# PSU2.net
KiCad netlist of a schematic drawn in Altium Designer
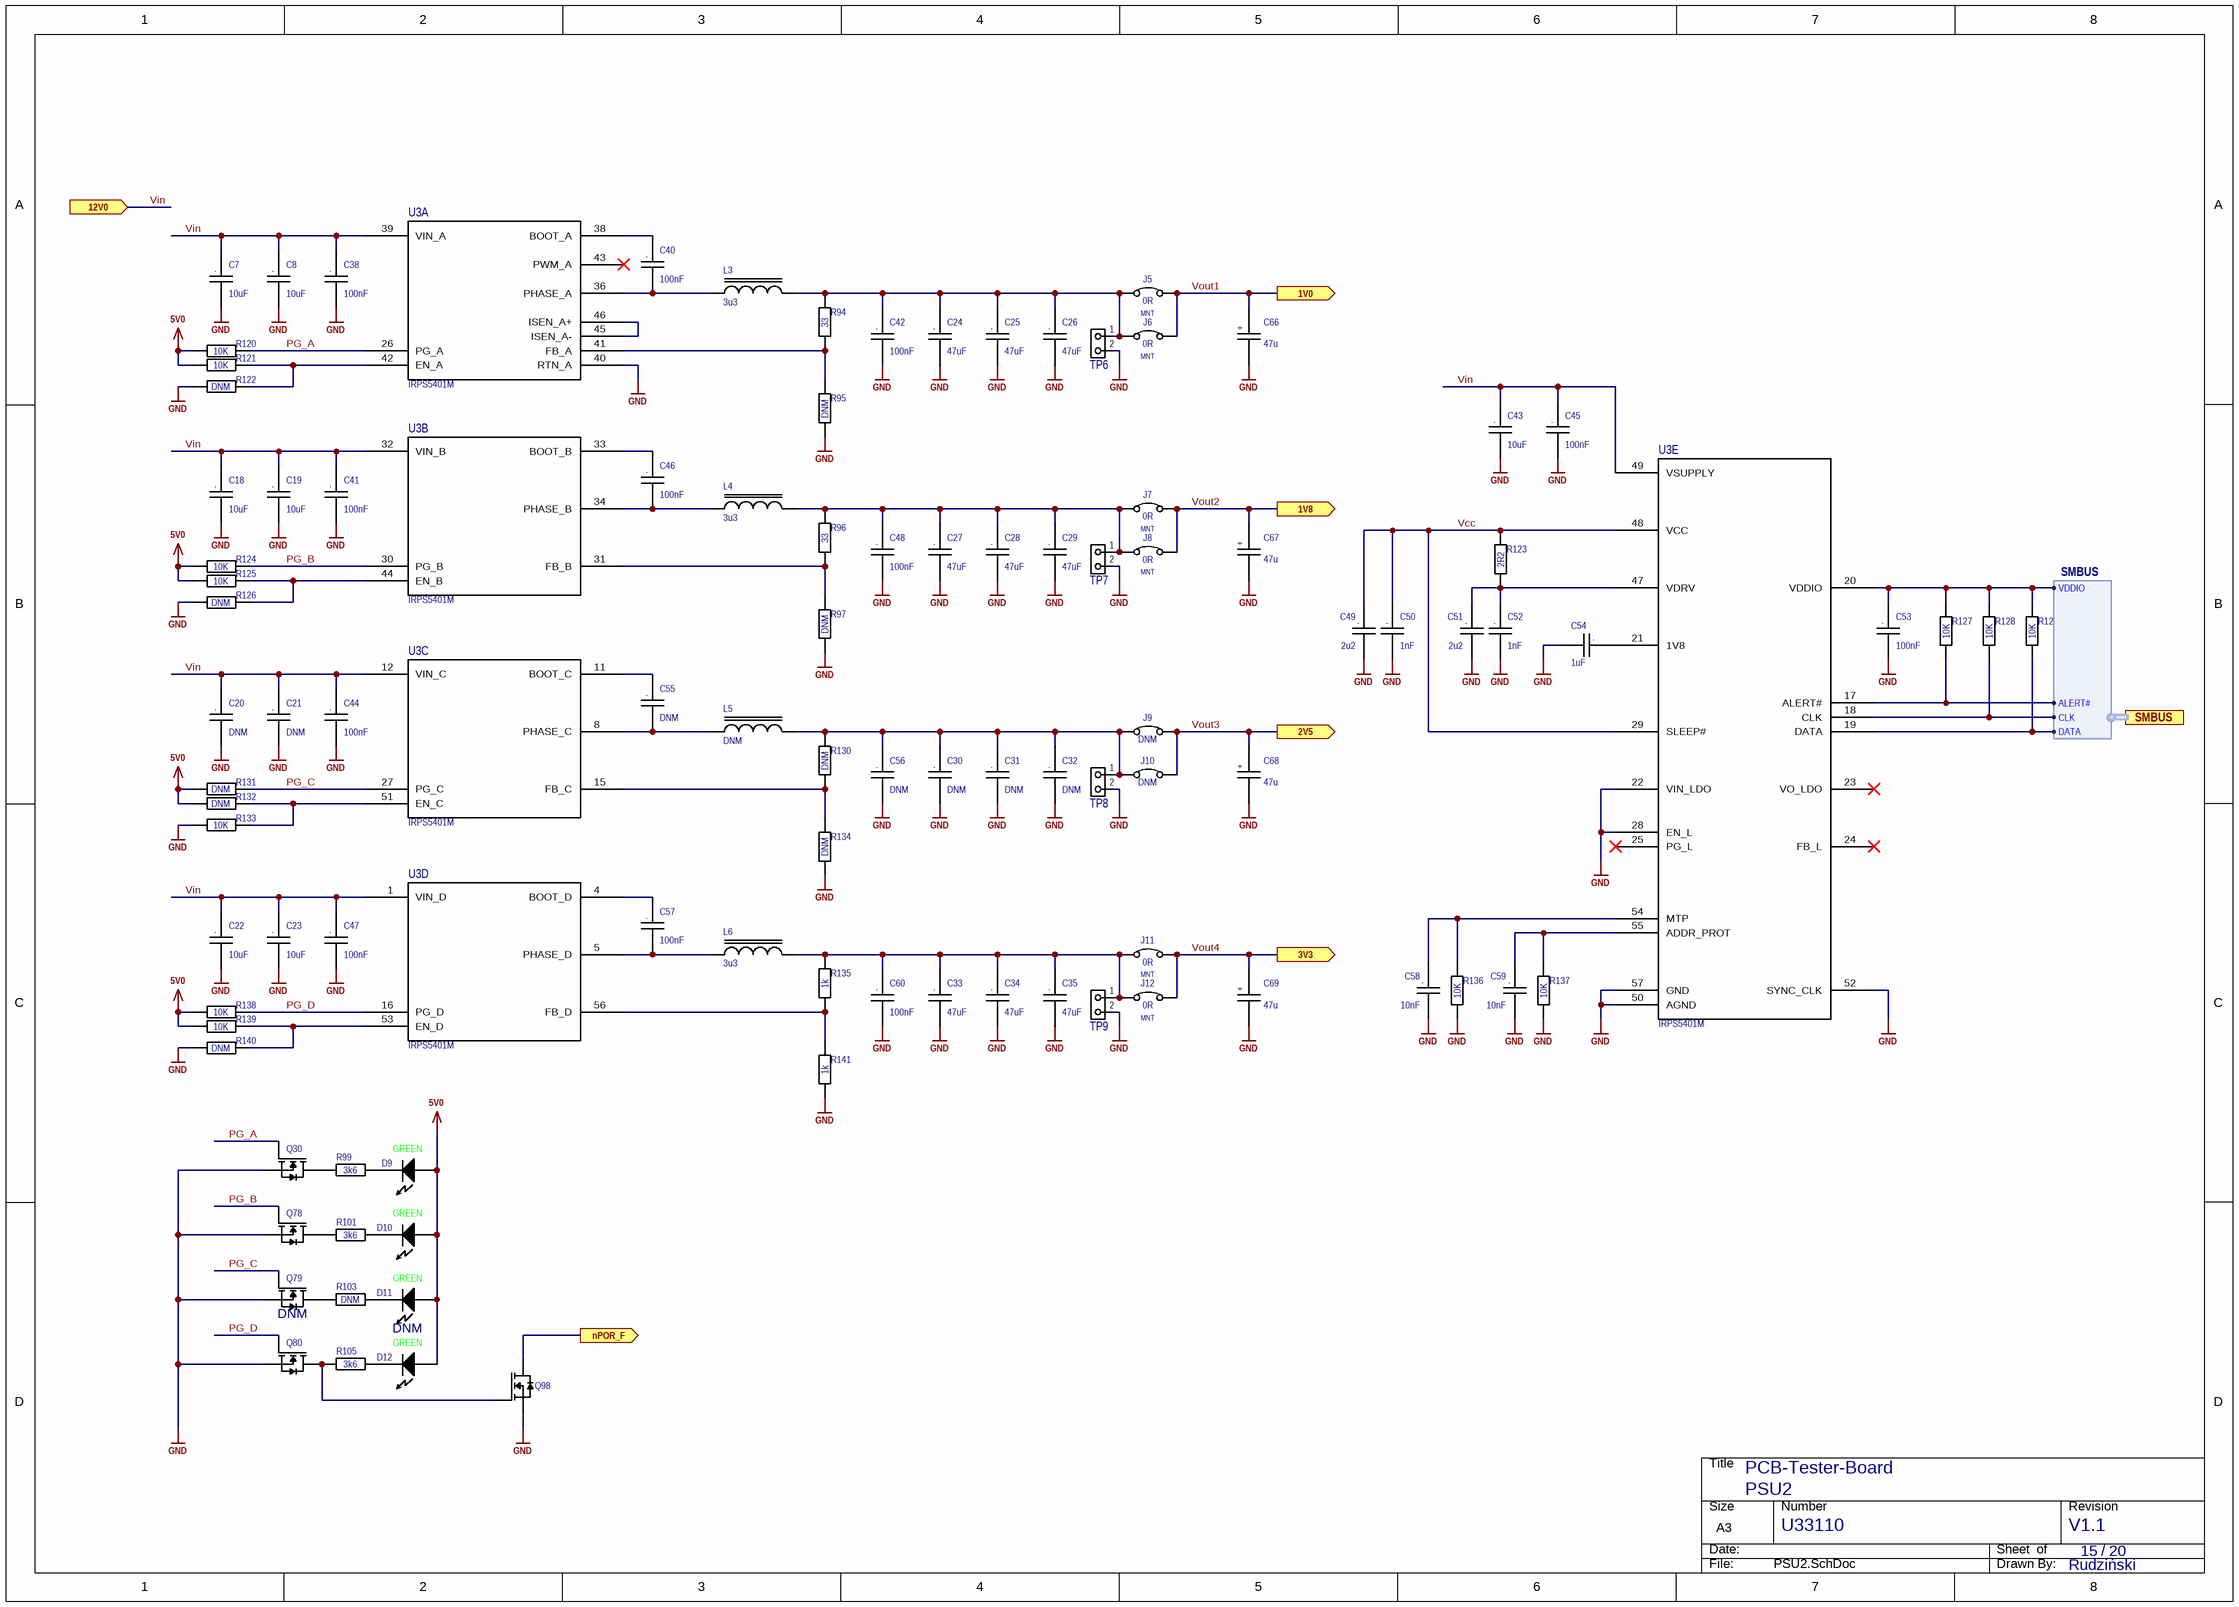
[diagram p0: PSU2.SchDoc]

(export (version "E")
  (design (tool "Eeschema 10.0.6"))
  (components
    (comp (ref "C7")
      (value "10uF")
      (footprint "C1206 Reflow")
      (description "CAP CER 10UF 25V X7R 1206")
      (fields
        (field (name "TOLERANCE") "±10%")
        (field (name "02. DISTRIBUTOR PART NUMBER") "445-7705-6-ND")
        (field (name "13. CREATED DATE/NAME") "AUG2018/Hören")
      )
      (libsource (lib "chickenfood") (part "C"))
    )
    (comp (ref "C8")
      (value "10uF")
      (footprint "C1206 Reflow")
      (description "CAP CER 10UF 25V X7R 1206")
      (fields
        (field (name "TOLERANCE") "±10%")
        (field (name "02. DISTRIBUTOR PART NUMBER") "445-7705-6-ND")
        (field (name "13. CREATED DATE/NAME") "AUG2018/Hören")
      )
      (libsource (lib "chickenfood") (part "C"))
    )
    (comp (ref "C18")
      (value "10uF")
      (footprint "C1206 Reflow")
      (description "CAP CER 10UF 25V X7R 1206")
      (fields
        (field (name "TOLERANCE") "±10%")
        (field (name "02. DISTRIBUTOR PART NUMBER") "445-7705-6-ND")
        (field (name "13. CREATED DATE/NAME") "AUG2018/Hören")
      )
      (libsource (lib "chickenfood") (part "C"))
    )
    (comp (ref "C19")
      (value "10uF")
      (footprint "C1206 Reflow")
      (description "CAP CER 10UF 25V X7R 1206")
      (fields
        (field (name "TOLERANCE") "±10%")
        (field (name "02. DISTRIBUTOR PART NUMBER") "445-7705-6-ND")
        (field (name "13. CREATED DATE/NAME") "AUG2018/Hören")
      )
      (libsource (lib "chickenfood") (part "C"))
    )
    (comp (ref "C20")
      (value "DNM")
      (footprint "C1206 Reflow")
      (description "CAP CER 10UF 25V X7R 1206")
      (fields
        (field (name "TOLERANCE") "±10%")
        (field (name "02. DISTRIBUTOR PART NUMBER") "445-7705-6-ND")
        (field (name "13. CREATED DATE/NAME") "AUG2018/Hören")
      )
      (libsource (lib "chickenfood") (part "C"))
    )
    (comp (ref "C21")
      (value "DNM")
      (footprint "C1206 Reflow")
      (description "CAP CER 10UF 25V X7R 1206")
      (fields
        (field (name "TOLERANCE") "±10%")
        (field (name "02. DISTRIBUTOR PART NUMBER") "445-7705-6-ND")
        (field (name "13. CREATED DATE/NAME") "AUG2018/Hören")
      )
      (libsource (lib "chickenfood") (part "C"))
    )
    (comp (ref "C22")
      (value "10uF")
      (footprint "C1206 Reflow")
      (description "CAP CER 10UF 25V X7R 1206")
      (fields
        (field (name "TOLERANCE") "±10%")
        (field (name "02. DISTRIBUTOR PART NUMBER") "445-7705-6-ND")
        (field (name "13. CREATED DATE/NAME") "AUG2018/Hören")
      )
      (libsource (lib "chickenfood") (part "C"))
    )
    (comp (ref "C23")
      (value "10uF")
      (footprint "C1206 Reflow")
      (description "CAP CER 10UF 25V X7R 1206")
      (fields
        (field (name "TOLERANCE") "±10%")
        (field (name "02. DISTRIBUTOR PART NUMBER") "445-7705-6-ND")
        (field (name "13. CREATED DATE/NAME") "AUG2018/Hören")
      )
      (libsource (lib "chickenfood") (part "C"))
    )
    (comp (ref "C24")
      (value "47uF")
      (footprint "C1210 Reflow")
      (description "CAP CER 47UF 10V X5R 1210")
      (fields
        (field (name "TOLERANCE") "±20%")
        (field (name "02. DISTRIBUTOR PART NUMBER") "1276-3380-6-ND")
        (field (name "13. CREATED DATE/NAME") "AUG2018/Hören")
      )
      (libsource (lib "chickenfood") (part "C"))
    )
    (comp (ref "C25")
      (value "47uF")
      (footprint "C1210 Reflow")
      (description "CAP CER 47UF 10V X5R 1210")
      (fields
        (field (name "TOLERANCE") "±20%")
        (field (name "02. DISTRIBUTOR PART NUMBER") "1276-3380-6-ND")
        (field (name "13. CREATED DATE/NAME") "AUG2018/Hören")
      )
      (libsource (lib "chickenfood") (part "C"))
    )
    (comp (ref "C26")
      (value "47uF")
      (footprint "C1210 Reflow")
      (description "CAP CER 47UF 10V X5R 1210")
      (fields
        (field (name "TOLERANCE") "±20%")
        (field (name "02. DISTRIBUTOR PART NUMBER") "1276-3380-6-ND")
        (field (name "13. CREATED DATE/NAME") "AUG2018/Hören")
      )
      (libsource (lib "chickenfood") (part "C"))
    )
    (comp (ref "C27")
      (value "47uF")
      (footprint "C1210 Reflow")
      (description "CAP CER 47UF 10V X5R 1210")
      (fields
        (field (name "TOLERANCE") "±20%")
        (field (name "02. DISTRIBUTOR PART NUMBER") "1276-3380-6-ND")
        (field (name "13. CREATED DATE/NAME") "AUG2018/Hören")
      )
      (libsource (lib "chickenfood") (part "C"))
    )
    (comp (ref "C28")
      (value "47uF")
      (footprint "C1210 Reflow")
      (description "CAP CER 47UF 10V X5R 1210")
      (fields
        (field (name "TOLERANCE") "±20%")
        (field (name "02. DISTRIBUTOR PART NUMBER") "1276-3380-6-ND")
        (field (name "13. CREATED DATE/NAME") "AUG2018/Hören")
      )
      (libsource (lib "chickenfood") (part "C"))
    )
    (comp (ref "C29")
      (value "47uF")
      (footprint "C1210 Reflow")
      (description "CAP CER 47UF 10V X5R 1210")
      (fields
        (field (name "TOLERANCE") "±20%")
        (field (name "02. DISTRIBUTOR PART NUMBER") "1276-3380-6-ND")
        (field (name "13. CREATED DATE/NAME") "AUG2018/Hören")
      )
      (libsource (lib "chickenfood") (part "C"))
    )
    (comp (ref "C30")
      (value "DNM")
      (footprint "C1210 Reflow")
      (description "CAP CER 47UF 10V X5R 1210")
      (fields
        (field (name "TOLERANCE") "±20%")
        (field (name "02. DISTRIBUTOR PART NUMBER") "1276-3380-6-ND")
        (field (name "13. CREATED DATE/NAME") "AUG2018/Hören")
      )
      (libsource (lib "chickenfood") (part "C"))
    )
    (comp (ref "C31")
      (value "DNM")
      (footprint "C1210 Reflow")
      (description "CAP CER 47UF 10V X5R 1210")
      (fields
        (field (name "TOLERANCE") "±20%")
        (field (name "02. DISTRIBUTOR PART NUMBER") "1276-3380-6-ND")
        (field (name "13. CREATED DATE/NAME") "AUG2018/Hören")
      )
      (libsource (lib "chickenfood") (part "C"))
    )
    (comp (ref "C32")
      (value "DNM")
      (footprint "C1210 Reflow")
      (description "CAP CER 47UF 10V X5R 1210")
      (fields
        (field (name "TOLERANCE") "±20%")
        (field (name "02. DISTRIBUTOR PART NUMBER") "1276-3380-6-ND")
        (field (name "13. CREATED DATE/NAME") "AUG2018/Hören")
      )
      (libsource (lib "chickenfood") (part "C"))
    )
    (comp (ref "C33")
      (value "47uF")
      (footprint "C1210 Reflow")
      (description "CAP CER 47UF 10V X5R 1210")
      (fields
        (field (name "TOLERANCE") "±20%")
        (field (name "02. DISTRIBUTOR PART NUMBER") "1276-3380-6-ND")
        (field (name "13. CREATED DATE/NAME") "AUG2018/Hören")
      )
      (libsource (lib "chickenfood") (part "C"))
    )
    (comp (ref "C34")
      (value "47uF")
      (footprint "C1210 Reflow")
      (description "CAP CER 47UF 10V X5R 1210")
      (fields
        (field (name "TOLERANCE") "±20%")
        (field (name "02. DISTRIBUTOR PART NUMBER") "1276-3380-6-ND")
        (field (name "13. CREATED DATE/NAME") "AUG2018/Hören")
      )
      (libsource (lib "chickenfood") (part "C"))
    )
    (comp (ref "C35")
      (value "47uF")
      (footprint "C1210 Reflow")
      (description "CAP CER 47UF 10V X5R 1210")
      (fields
        (field (name "TOLERANCE") "±20%")
        (field (name "02. DISTRIBUTOR PART NUMBER") "1276-3380-6-ND")
        (field (name "13. CREATED DATE/NAME") "AUG2018/Hören")
      )
      (libsource (lib "chickenfood") (part "C"))
    )
    (comp (ref "C38")
      (value "100nF")
      (footprint "C0402 Reflow")
      (description "CAP CER 0.1UF 25V X7R 0402")
      (fields
        (field (name "TOLERANCE") "±10%")
        (field (name "02. DISTRIBUTOR PART NUMBER") "311-2077-6-ND")
        (field (name "13. CREATED DATE/NAME") "AUG2018/Hören")
      )
      (libsource (lib "chickenfood") (part "C"))
    )
    (comp (ref "C40")
      (value "100nF")
      (footprint "C0402 Reflow")
      (description "CAP CER 0.1UF 25V X7R 0402")
      (fields
        (field (name "TOLERANCE") "±10%")
        (field (name "02. DISTRIBUTOR PART NUMBER") "311-2077-6-ND")
        (field (name "13. CREATED DATE/NAME") "AUG2018/Hören")
      )
      (libsource (lib "chickenfood") (part "C"))
    )
    (comp (ref "C41")
      (value "100nF")
      (footprint "C0402 Reflow")
      (description "CAP CER 0.1UF 25V X7R 0402")
      (fields
        (field (name "TOLERANCE") "±10%")
        (field (name "02. DISTRIBUTOR PART NUMBER") "311-2077-6-ND")
        (field (name "13. CREATED DATE/NAME") "AUG2018/Hören")
      )
      (libsource (lib "chickenfood") (part "C"))
    )
    (comp (ref "C42")
      (value "100nF")
      (footprint "C0402 Reflow")
      (description "CAP CER 0.1UF 25V X7R 0402")
      (fields
        (field (name "TOLERANCE") "±10%")
        (field (name "02. DISTRIBUTOR PART NUMBER") "311-2077-6-ND")
        (field (name "13. CREATED DATE/NAME") "AUG2018/Hören")
      )
      (libsource (lib "chickenfood") (part "C"))
    )
    (comp (ref "C43")
      (value "10uF")
      (footprint "C1206 Reflow")
      (description "CAP CER 10UF 25V X7R 1206")
      (fields
        (field (name "TOLERANCE") "±10%")
        (field (name "02. DISTRIBUTOR PART NUMBER") "445-7705-6-ND")
        (field (name "13. CREATED DATE/NAME") "AUG2018/Hören")
      )
      (libsource (lib "chickenfood") (part "C"))
    )
    (comp (ref "C44")
      (value "100nF")
      (footprint "C0402 Reflow")
      (description "CAP CER 0.1UF 25V X7R 0402")
      (fields
        (field (name "TOLERANCE") "±10%")
        (field (name "02. DISTRIBUTOR PART NUMBER") "311-2077-6-ND")
        (field (name "13. CREATED DATE/NAME") "AUG2018/Hören")
      )
      (libsource (lib "chickenfood") (part "C"))
    )
    (comp (ref "C45")
      (value "100nF")
      (footprint "C0402 Reflow")
      (description "CAP CER 0.1UF 25V X7R 0402")
      (fields
        (field (name "TOLERANCE") "±10%")
        (field (name "02. DISTRIBUTOR PART NUMBER") "311-2077-6-ND")
        (field (name "13. CREATED DATE/NAME") "AUG2018/Hören")
      )
      (libsource (lib "chickenfood") (part "C"))
    )
    (comp (ref "C46")
      (value "100nF")
      (footprint "C0402 Reflow")
      (description "CAP CER 0.1UF 25V X7R 0402")
      (fields
        (field (name "TOLERANCE") "±10%")
        (field (name "02. DISTRIBUTOR PART NUMBER") "311-2077-6-ND")
        (field (name "13. CREATED DATE/NAME") "AUG2018/Hören")
      )
      (libsource (lib "chickenfood") (part "C"))
    )
    (comp (ref "C47")
      (value "100nF")
      (footprint "C0402 Reflow")
      (description "CAP CER 0.1UF 25V X7R 0402")
      (fields
        (field (name "TOLERANCE") "±10%")
        (field (name "02. DISTRIBUTOR PART NUMBER") "311-2077-6-ND")
        (field (name "13. CREATED DATE/NAME") "AUG2018/Hören")
      )
      (libsource (lib "chickenfood") (part "C"))
    )
    (comp (ref "C48")
      (value "100nF")
      (footprint "C0402 Reflow")
      (description "CAP CER 0.1UF 25V X7R 0402")
      (fields
        (field (name "TOLERANCE") "±10%")
        (field (name "02. DISTRIBUTOR PART NUMBER") "311-2077-6-ND")
        (field (name "13. CREATED DATE/NAME") "AUG2018/Hören")
      )
      (libsource (lib "chickenfood") (part "C"))
    )
    (comp (ref "C49")
      (value "2u2")
      (footprint "C0805 Reflow")
      (description "CAP CER 2.2UF 10V X7R 0805")
      (fields
        (field (name "02. DISTRIBUTOR PART NUMBER") "1276-1188-1-ND")
        (field (name "07. MANUFACTURER  PART NUMBER") "CL21B225KPFNNNE")
      )
      (libsource (lib "PCB-Tester-Board-V1") (part "C_11"))
    )
    (comp (ref "C50")
      (value "1nF")
      (footprint "C0402 Reflow")
      (description "CAP CER 1000PF 25V X7R 0402")
      (fields
        (field (name "TOLERANCE") "±10%")
        (field (name "02. DISTRIBUTOR PART NUMBER") "399-1031-6-ND")
        (field (name "13. CREATED DATE/NAME") "AUG2018/Hören")
      )
      (libsource (lib "PCB-Tester-Board-V1") (part "C_7"))
    )
    (comp (ref "C51")
      (value "2u2")
      (footprint "C0805 Reflow")
      (description "CAP CER 2.2UF 10V X7R 0805")
      (fields
        (field (name "02. DISTRIBUTOR PART NUMBER") "1276-1188-1-ND")
        (field (name "07. MANUFACTURER  PART NUMBER") "CL21B225KPFNNNE")
      )
      (libsource (lib "PCB-Tester-Board-V1") (part "C_11"))
    )
    (comp (ref "C52")
      (value "1nF")
      (footprint "C0402 Reflow")
      (description "CAP CER 1000PF 25V X7R 0402")
      (fields
        (field (name "TOLERANCE") "±10%")
        (field (name "02. DISTRIBUTOR PART NUMBER") "399-1031-6-ND")
        (field (name "13. CREATED DATE/NAME") "AUG2018/Hören")
      )
      (libsource (lib "PCB-Tester-Board-V1") (part "C_7"))
    )
    (comp (ref "C53")
      (value "100nF")
      (footprint "C0402 Reflow")
      (description "CAP CER 0.1UF 25V X7R 0402")
      (fields
        (field (name "TOLERANCE") "±10%")
        (field (name "02. DISTRIBUTOR PART NUMBER") "311-2077-6-ND")
        (field (name "13. CREATED DATE/NAME") "AUG2018/Hören")
      )
      (libsource (lib "chickenfood") (part "C"))
    )
    (comp (ref "C54")
      (value "1uF")
      (footprint "C0402 Reflow")
      (description "CAP CER 1UF 6.3V X7R 0402")
      (fields
        (field (name "TOLERANCE") "±10%")
        (field (name "02. DISTRIBUTOR PART NUMBER") "490-13339-6-ND")
        (field (name "13. CREATED DATE/NAME") "AUG2018/Hören")
      )
      (libsource (lib "PCB-Tester-Board-V1") (part "C_2"))
    )
    (comp (ref "C55")
      (value "DNM")
      (footprint "C0402 Reflow")
      (description "CAP CER 0.1UF 25V X7R 0402")
      (fields
        (field (name "TOLERANCE") "±10%")
        (field (name "02. DISTRIBUTOR PART NUMBER") "311-2077-6-ND")
        (field (name "13. CREATED DATE/NAME") "AUG2018/Hören")
      )
      (libsource (lib "chickenfood") (part "C"))
    )
    (comp (ref "C56")
      (value "DNM")
      (footprint "C0402 Reflow")
      (description "CAP CER 0.1UF 25V X7R 0402")
      (fields
        (field (name "TOLERANCE") "±10%")
        (field (name "02. DISTRIBUTOR PART NUMBER") "311-2077-6-ND")
        (field (name "13. CREATED DATE/NAME") "AUG2018/Hören")
      )
      (libsource (lib "chickenfood") (part "C"))
    )
    (comp (ref "C57")
      (value "100nF")
      (footprint "C0402 Reflow")
      (description "CAP CER 0.1UF 25V X7R 0402")
      (fields
        (field (name "TOLERANCE") "±10%")
        (field (name "02. DISTRIBUTOR PART NUMBER") "311-2077-6-ND")
        (field (name "13. CREATED DATE/NAME") "AUG2018/Hören")
      )
      (libsource (lib "chickenfood") (part "C"))
    )
    (comp (ref "C58")
      (value "10nF")
      (footprint "C0402 Reflow")
      (description "CAP CER 0.01UF 25V X7R 0402")
      (fields (field (name "TOLERANCE") "±10%") (field (name "02. DISTRIBUTOR PART NUMBER") "490-6043-1-ND"))
      (libsource (lib "PCB-Tester-Board-V1") (part "C_10"))
    )
    (comp (ref "C59")
      (value "10nF")
      (footprint "C0402 Reflow")
      (description "CAP CER 0.01UF 25V X7R 0402")
      (fields (field (name "TOLERANCE") "±10%") (field (name "02. DISTRIBUTOR PART NUMBER") "490-6043-1-ND"))
      (libsource (lib "PCB-Tester-Board-V1") (part "C_10"))
    )
    (comp (ref "C60")
      (value "100nF")
      (footprint "C0402 Reflow")
      (description "CAP CER 0.1UF 25V X7R 0402")
      (fields
        (field (name "TOLERANCE") "±10%")
        (field (name "02. DISTRIBUTOR PART NUMBER") "311-2077-6-ND")
        (field (name "13. CREATED DATE/NAME") "AUG2018/Hören")
      )
      (libsource (lib "chickenfood") (part "C"))
    )
    (comp (ref "C66")
      (value "47u")
      (footprint "CAP_TAN_B")
      (description "CAP TANT 47UF 20% 10V 1411")
      (fields
        (field (name "02. DISTRIBUTOR PART NUMBER") "478-12531-1-ND")
        (field (name "07. MANUFACTURER  PART NUMBER") "F971A476MBAHT3")
      )
      (libsource (lib "PCB-Tester-Board-V1") (part "C+_TAN"))
    )
    (comp (ref "C67")
      (value "47u")
      (footprint "CAP_TAN_B")
      (description "CAP TANT 47UF 20% 10V 1411")
      (fields
        (field (name "02. DISTRIBUTOR PART NUMBER") "478-12531-1-ND")
        (field (name "07. MANUFACTURER  PART NUMBER") "F971A476MBAHT3")
      )
      (libsource (lib "PCB-Tester-Board-V1") (part "C+_TAN"))
    )
    (comp (ref "C68")
      (value "47u")
      (footprint "CAP_TAN_B")
      (description "CAP TANT 47UF 20% 10V 1411")
      (fields
        (field (name "02. DISTRIBUTOR PART NUMBER") "478-12531-1-ND")
        (field (name "07. MANUFACTURER  PART NUMBER") "F971A476MBAHT3")
      )
      (libsource (lib "PCB-Tester-Board-V1") (part "C+_TAN"))
    )
    (comp (ref "C69")
      (value "47u")
      (footprint "CAP_TAN_B")
      (description "CAP TANT 47UF 20% 10V 1411")
      (fields
        (field (name "02. DISTRIBUTOR PART NUMBER") "478-12531-1-ND")
        (field (name "07. MANUFACTURER  PART NUMBER") "F971A476MBAHT3")
      )
      (libsource (lib "PCB-Tester-Board-V1") (part "C+_TAN"))
    )
    (comp (ref "D9")
      (value "D")
      (footprint "L0603G")
      (description "LED GREEN DIFFUSED 0603 SMD")
      (fields
        (field (name "02. DISTRIBUTOR PART NUMBER") "475-2709-6-ND")
        (field (name "07. MANUFACTURER  PART NUMBER") "LG L29K-G2J1-24-Z")
        (field (name "COLOR") "GREEN")
        (field (name "13. CREATED DATE/NAME") "AUG2018/Hören")
      )
      (libsource (lib "chickenfood") (part "LED"))
    )
    (comp (ref "D10")
      (value "D")
      (footprint "L0603G")
      (description "LED GREEN DIFFUSED 0603 SMD")
      (fields
        (field (name "02. DISTRIBUTOR PART NUMBER") "475-2709-6-ND")
        (field (name "07. MANUFACTURER  PART NUMBER") "LG L29K-G2J1-24-Z")
        (field (name "COLOR") "GREEN")
        (field (name "13. CREATED DATE/NAME") "AUG2018/Hören")
      )
      (libsource (lib "chickenfood") (part "LED"))
    )
    (comp (ref "D11")
      (value "D")
      (footprint "L0603G")
      (description "LED GREEN DIFFUSED 0603 SMD")
      (fields
        (field (name "02. DISTRIBUTOR PART NUMBER") "475-2709-6-ND")
        (field (name "07. MANUFACTURER  PART NUMBER") "LG L29K-G2J1-24-Z")
        (field (name "COLOR") "GREEN")
        (field (name "NICNAME") "DNM")
        (field (name "13. CREATED DATE/NAME") "AUG2018/Hören")
      )
      (libsource (lib "chickenfood") (part "LED"))
    )
    (comp (ref "D12")
      (value "D")
      (footprint "L0603G")
      (description "LED GREEN DIFFUSED 0603 SMD")
      (fields
        (field (name "02. DISTRIBUTOR PART NUMBER") "475-2709-6-ND")
        (field (name "07. MANUFACTURER  PART NUMBER") "LG L29K-G2J1-24-Z")
        (field (name "COLOR") "GREEN")
        (field (name "13. CREATED DATE/NAME") "AUG2018/Hören")
      )
      (libsource (lib "chickenfood") (part "LED"))
    )
    (comp (ref "J5")
      (value "0R")
      (footprint "JumperSMD")
      (description "RES SMD 0 OHM JUMPER 1/10W 0603")
      (fields
        (field (name "02. DISTRIBUTOR PART NUMBER") "311-0.0GRDKR-ND")
        (field (name "07. MANUFACTURER  PART NUMBER") "RC0603JR-070RL")
        (field (name "POPULATED") "MNT")
      )
      (libsource (lib "chickenfood") (part "Jumper SMD"))
    )
    (comp (ref "J6")
      (value "0R")
      (footprint "JumperSMD")
      (description "RES SMD 0 OHM JUMPER 1/10W 0603")
      (fields
        (field (name "02. DISTRIBUTOR PART NUMBER") "311-0.0GRDKR-ND")
        (field (name "07. MANUFACTURER  PART NUMBER") "RC0603JR-070RL")
        (field (name "POPULATED") "MNT")
      )
      (libsource (lib "chickenfood") (part "Jumper SMD"))
    )
    (comp (ref "J7")
      (value "0R")
      (footprint "JumperSMD")
      (description "RES SMD 0 OHM JUMPER 1/10W 0603")
      (fields
        (field (name "02. DISTRIBUTOR PART NUMBER") "311-0.0GRDKR-ND")
        (field (name "07. MANUFACTURER  PART NUMBER") "RC0603JR-070RL")
        (field (name "POPULATED") "MNT")
      )
      (libsource (lib "chickenfood") (part "Jumper SMD"))
    )
    (comp (ref "J8")
      (value "0R")
      (footprint "JumperSMD")
      (description "RES SMD 0 OHM JUMPER 1/10W 0603")
      (fields
        (field (name "02. DISTRIBUTOR PART NUMBER") "311-0.0GRDKR-ND")
        (field (name "07. MANUFACTURER  PART NUMBER") "RC0603JR-070RL")
        (field (name "POPULATED") "MNT")
      )
      (libsource (lib "chickenfood") (part "Jumper SMD"))
    )
    (comp (ref "J9")
      (value "DNM")
      (footprint "JumperSMD")
      (description "RES SMD 0 OHM JUMPER 1/10W 0603")
      (fields
        (field (name "02. DISTRIBUTOR PART NUMBER") "311-0.0GRDKR-ND")
        (field (name "07. MANUFACTURER  PART NUMBER") "RC0603JR-070RL")
      )
      (libsource (lib "chickenfood") (part "Jumper SMD"))
    )
    (comp (ref "J10")
      (value "DNM")
      (footprint "JumperSMD")
      (description "RES SMD 0 OHM JUMPER 1/10W 0603")
      (fields
        (field (name "02. DISTRIBUTOR PART NUMBER") "311-0.0GRDKR-ND")
        (field (name "07. MANUFACTURER  PART NUMBER") "RC0603JR-070RL")
      )
      (libsource (lib "chickenfood") (part "Jumper SMD"))
    )
    (comp (ref "J11")
      (value "0R")
      (footprint "JumperSMD")
      (description "RES SMD 0 OHM JUMPER 1/10W 0603")
      (fields
        (field (name "02. DISTRIBUTOR PART NUMBER") "311-0.0GRDKR-ND")
        (field (name "07. MANUFACTURER  PART NUMBER") "RC0603JR-070RL")
        (field (name "POPULATED") "MNT")
      )
      (libsource (lib "chickenfood") (part "Jumper SMD"))
    )
    (comp (ref "J12")
      (value "0R")
      (footprint "JumperSMD")
      (description "RES SMD 0 OHM JUMPER 1/10W 0603")
      (fields
        (field (name "02. DISTRIBUTOR PART NUMBER") "311-0.0GRDKR-ND")
        (field (name "07. MANUFACTURER  PART NUMBER") "RC0603JR-070RL")
        (field (name "POPULATED") "MNT")
      )
      (libsource (lib "chickenfood") (part "Jumper SMD"))
    )
    (comp (ref "L3")
      (value "L")
      (footprint "XAL7070")
      (description "Fixed Inductors 3.3uH Shld 20% 15.1A 9.42mOhms AECQ2")
      (fields
        (field (name "02. DISTRIBUTOR PART NUMBER") "994-XAL7070-332MEC")
        (field (name "07. MANUFACTURER  PART NUMBER") "XAL7070-332MEC")
        (field (name "INDUCTANCE") "3u3")
      )
      (libsource (lib "PCB-Tester-Board-V1") (part "INDUCTOR"))
    )
    (comp (ref "L4")
      (value "L")
      (footprint "XAL7070")
      (description "Fixed Inductors 3.3uH Shld 20% 15.1A 9.42mOhms AECQ2")
      (fields
        (field (name "02. DISTRIBUTOR PART NUMBER") "994-XAL7070-332MEC")
        (field (name "07. MANUFACTURER  PART NUMBER") "XAL7070-332MEC")
        (field (name "INDUCTANCE") "3u3")
      )
      (libsource (lib "PCB-Tester-Board-V1") (part "INDUCTOR"))
    )
    (comp (ref "L5")
      (value "L")
      (footprint "XAL7070")
      (description "Fixed Inductors 3.3uH Shld 20% 15.1A 9.42mOhms AECQ2")
      (fields
        (field (name "02. DISTRIBUTOR PART NUMBER") "994-XAL7070-332MEC")
        (field (name "07. MANUFACTURER  PART NUMBER") "XAL7070-332MEC")
        (field (name "INDUCTANCE") "DNM")
      )
      (libsource (lib "PCB-Tester-Board-V1") (part "INDUCTOR"))
    )
    (comp (ref "L6")
      (value "L")
      (footprint "XAL7070")
      (description "Fixed Inductors 3.3uH Shld 20% 15.1A 9.42mOhms AECQ2")
      (fields
        (field (name "02. DISTRIBUTOR PART NUMBER") "994-XAL7070-332MEC")
        (field (name "07. MANUFACTURER  PART NUMBER") "XAL7070-332MEC")
        (field (name "INDUCTANCE") "3u3")
      )
      (libsource (lib "PCB-Tester-Board-V1") (part "INDUCTOR"))
    )
    (comp (ref "Q30")
      (value "Q")
      (footprint "SOT23-3")
      (description "MOSFET N-CH 25V 680MA SOT-23")
      (fields
        (field (name "02. DISTRIBUTOR PART NUMBER") "FDV303NDKR-ND")
        (field (name "07. MANUFACTURER  PART NUMBER") "FDV303N")
        (field (name "13. CREATED DATE/NAME") "AUG 2018 / Hören")
      )
      (libsource (lib "PCB-Tester-Board-V1") (part "FDV303N"))
    )
    (comp (ref "Q78")
      (value "Q")
      (footprint "SOT23-3")
      (description "MOSFET N-CH 25V 680MA SOT-23")
      (fields
        (field (name "02. DISTRIBUTOR PART NUMBER") "FDV303NDKR-ND")
        (field (name "07. MANUFACTURER  PART NUMBER") "FDV303N")
        (field (name "13. CREATED DATE/NAME") "AUG 2018 / Hören")
      )
      (libsource (lib "PCB-Tester-Board-V1") (part "FDV303N"))
    )
    (comp (ref "Q79")
      (value "Q")
      (footprint "SOT23-3")
      (description "MOSFET N-CH 25V 680MA SOT-23")
      (fields
        (field (name "02. DISTRIBUTOR PART NUMBER") "FDV303NDKR-ND")
        (field (name "07. MANUFACTURER  PART NUMBER") "FDV303N")
        (field (name "NICNAME") "DNM")
        (field (name "13. CREATED DATE/NAME") "AUG 2018 / Hören")
      )
      (libsource (lib "PCB-Tester-Board-V1") (part "FDV303N"))
    )
    (comp (ref "Q80")
      (value "Q")
      (footprint "SOT23-3")
      (description "MOSFET N-CH 25V 680MA SOT-23")
      (fields
        (field (name "02. DISTRIBUTOR PART NUMBER") "FDV303NDKR-ND")
        (field (name "07. MANUFACTURER  PART NUMBER") "FDV303N")
        (field (name "13. CREATED DATE/NAME") "AUG 2018 / Hören")
      )
      (libsource (lib "PCB-Tester-Board-V1") (part "FDV303N"))
    )
    (comp (ref "Q98")
      (value "Q")
      (footprint "SOT23-3")
      (description "MOSFET N-CH 25V 680MA SOT-23")
      (fields
        (field (name "02. DISTRIBUTOR PART NUMBER") "FDV303NDKR-ND")
        (field (name "07. MANUFACTURER  PART NUMBER") "FDV303N")
        (field (name "13. CREATED DATE/NAME") "AUG 2018 / Hören")
      )
      (libsource (lib "PCB-Tester-Board-V1") (part "FDV303N"))
    )
    (comp (ref "R94")
      (value "33")
      (footprint "R0402 Reflow")
      (description "RES SMD 33 OHM 1% 1/16W 0402")
      (fields
        (field (name "TOLERANCE") "±1%")
        (field (name "02. DISTRIBUTOR PART NUMBER") "311-33.0LRDKR-ND")
        (field (name "13. CREATED DATE/NAME") "AUG2018/Hören")
      )
      (libsource (lib "chickenfood") (part "R"))
    )
    (comp (ref "R95")
      (value "DNM")
      (footprint "R0402 Reflow")
      (description "RES SMD 10K OHM 1% 1/16W 0402")
      (fields
        (field (name "TOLERANCE") "±1%")
        (field (name "02. DISTRIBUTOR PART NUMBER") "311-10.0KLRDKR-ND")
        (field (name "13. CREATED DATE/NAME") "AUG2018/Hören")
      )
      (libsource (lib "chickenfood") (part "R"))
    )
    (comp (ref "R96")
      (value "33")
      (footprint "R0402 Reflow")
      (description "RES SMD 33 OHM 1% 1/16W 0402")
      (fields
        (field (name "TOLERANCE") "±1%")
        (field (name "02. DISTRIBUTOR PART NUMBER") "311-33.0LRDKR-ND")
        (field (name "13. CREATED DATE/NAME") "AUG2018/Hören")
      )
      (libsource (lib "chickenfood") (part "R"))
    )
    (comp (ref "R97")
      (value "DNM")
      (footprint "R0402 Reflow")
      (description "RES SMD 10K OHM 1% 1/16W 0402")
      (fields
        (field (name "TOLERANCE") "±1%")
        (field (name "02. DISTRIBUTOR PART NUMBER") "311-10.0KLRDKR-ND")
        (field (name "13. CREATED DATE/NAME") "AUG2018/Hören")
      )
      (libsource (lib "chickenfood") (part "R"))
    )
    (comp (ref "R99")
      (value "3k6")
      (footprint "R0603 Reflow")
      (description "RES SMD 3.6K OHM 1% 1/10W 0603")
      (fields
        (field (name "TOLERANCE") "±1%")
        (field (name "02. DISTRIBUTOR PART NUMBER") "311-3.60KHRCT-ND")
        (field (name "13. CREATED DATE/NAME") "AUG2018/Hören")
      )
      (libsource (lib "") (part "R_1"))
    )
    (comp (ref "R101")
      (value "3k6")
      (footprint "R0603 Reflow")
      (description "RES SMD 3.6K OHM 1% 1/10W 0603")
      (fields
        (field (name "TOLERANCE") "±1%")
        (field (name "02. DISTRIBUTOR PART NUMBER") "311-3.60KHRCT-ND")
        (field (name "13. CREATED DATE/NAME") "AUG2018/Hören")
      )
      (libsource (lib "") (part "R_1"))
    )
    (comp (ref "R103")
      (value "DNM")
      (footprint "R0603 Reflow")
      (description "RES SMD 1.65K OHM 1% 1/16W 0402")
      (fields
        (field (name "TOLERANCE") "±1%")
        (field (name "02. DISTRIBUTOR PART NUMBER") "YAG3043DKR-ND")
        (field (name "13. CREATED DATE/NAME") "AUG2018/Hören")
      )
      (libsource (lib "") (part "R_1"))
    )
    (comp (ref "R105")
      (value "3k6")
      (footprint "R0603 Reflow")
      (description "RES SMD 3.6K OHM 1% 1/10W 0603")
      (fields
        (field (name "TOLERANCE") "±1%")
        (field (name "02. DISTRIBUTOR PART NUMBER") "311-3.60KHRCT-ND")
        (field (name "13. CREATED DATE/NAME") "AUG2018/Hören")
      )
      (libsource (lib "") (part "R_1"))
    )
    (comp (ref "R120")
      (value "10K")
      (footprint "R0402 Reflow")
      (description "RES SMD 10K OHM 1% 1/16W 0402")
      (fields
        (field (name "TOLERANCE") "±1%")
        (field (name "02. DISTRIBUTOR PART NUMBER") "311-10.0KLRDKR-ND")
        (field (name "13. CREATED DATE/NAME") "AUG2018/Hören")
      )
      (libsource (lib "") (part "R_2"))
    )
    (comp (ref "R121")
      (value "10K")
      (footprint "R0402 Reflow")
      (description "RES SMD 10K OHM 1% 1/16W 0402")
      (fields
        (field (name "TOLERANCE") "±1%")
        (field (name "02. DISTRIBUTOR PART NUMBER") "311-10.0KLRDKR-ND")
        (field (name "13. CREATED DATE/NAME") "AUG2018/Hören")
      )
      (libsource (lib "") (part "R_2"))
    )
    (comp (ref "R122")
      (value "DNM")
      (footprint "R0402 Reflow")
      (description "RES SMD 10K OHM 1% 1/16W 0402")
      (fields
        (field (name "TOLERANCE") "±1%")
        (field (name "02. DISTRIBUTOR PART NUMBER") "311-10.0KLRDKR-ND")
        (field (name "13. CREATED DATE/NAME") "AUG2018/Hören")
      )
      (libsource (lib "") (part "R_2"))
    )
    (comp (ref "R123")
      (value "2R2")
      (footprint "R0402 Reflow")
      (description "RES SMD 2.2 OHM 1% 1/16W 0402")
      (fields (field (name "TOLERANCE") "±1%") (field (name "02. DISTRIBUTOR PART NUMBER") "311-2.20LRTR-ND"))
      (libsource (lib "PCB-Tester-Board-V1") (part "R_24"))
    )
    (comp (ref "R124")
      (value "10K")
      (footprint "R0402 Reflow")
      (description "RES SMD 10K OHM 1% 1/16W 0402")
      (fields
        (field (name "TOLERANCE") "±1%")
        (field (name "02. DISTRIBUTOR PART NUMBER") "311-10.0KLRDKR-ND")
        (field (name "13. CREATED DATE/NAME") "AUG2018/Hören")
      )
      (libsource (lib "") (part "R_2"))
    )
    (comp (ref "R125")
      (value "10K")
      (footprint "R0402 Reflow")
      (description "RES SMD 10K OHM 1% 1/16W 0402")
      (fields
        (field (name "TOLERANCE") "±1%")
        (field (name "02. DISTRIBUTOR PART NUMBER") "311-10.0KLRDKR-ND")
        (field (name "13. CREATED DATE/NAME") "AUG2018/Hören")
      )
      (libsource (lib "") (part "R_2"))
    )
    (comp (ref "R126")
      (value "DNM")
      (footprint "R0402 Reflow")
      (description "RES SMD 10K OHM 1% 1/16W 0402")
      (fields
        (field (name "TOLERANCE") "±1%")
        (field (name "02. DISTRIBUTOR PART NUMBER") "311-10.0KLRDKR-ND")
        (field (name "13. CREATED DATE/NAME") "AUG2018/Hören")
      )
      (libsource (lib "") (part "R_2"))
    )
    (comp (ref "R127")
      (value "10K")
      (footprint "R0402 Reflow")
      (description "RES SMD 10K OHM 1% 1/16W 0402")
      (fields
        (field (name "TOLERANCE") "±1%")
        (field (name "02. DISTRIBUTOR PART NUMBER") "311-10.0KLRDKR-ND")
        (field (name "13. CREATED DATE/NAME") "AUG2018/Hören")
      )
      (libsource (lib "chickenfood") (part "R"))
    )
    (comp (ref "R128")
      (value "10K")
      (footprint "R0402 Reflow")
      (description "RES SMD 10K OHM 1% 1/16W 0402")
      (fields
        (field (name "TOLERANCE") "±1%")
        (field (name "02. DISTRIBUTOR PART NUMBER") "311-10.0KLRDKR-ND")
        (field (name "13. CREATED DATE/NAME") "AUG2018/Hören")
      )
      (libsource (lib "chickenfood") (part "R"))
    )
    (comp (ref "R129")
      (value "10K")
      (footprint "R0402 Reflow")
      (description "RES SMD 10K OHM 1% 1/16W 0402")
      (fields
        (field (name "TOLERANCE") "±1%")
        (field (name "02. DISTRIBUTOR PART NUMBER") "311-10.0KLRDKR-ND")
        (field (name "13. CREATED DATE/NAME") "AUG2018/Hören")
      )
      (libsource (lib "chickenfood") (part "R"))
    )
    (comp (ref "R130")
      (value "DNM")
      (footprint "R0402 Reflow")
      (description "RES SMD 10K OHM 1% 1/16W 0402")
      (fields
        (field (name "TOLERANCE") "±1%")
        (field (name "02. DISTRIBUTOR PART NUMBER") "311-10.0KLRDKR-ND")
        (field (name "13. CREATED DATE/NAME") "AUG2018/Hören")
      )
      (libsource (lib "chickenfood") (part "R"))
    )
    (comp (ref "R131")
      (value "DNM")
      (footprint "R0402 Reflow")
      (description "RES SMD 10K OHM 1% 1/16W 0402")
      (fields
        (field (name "TOLERANCE") "±1%")
        (field (name "02. DISTRIBUTOR PART NUMBER") "311-10.0KLRDKR-ND")
        (field (name "13. CREATED DATE/NAME") "AUG2018/Hören")
      )
      (libsource (lib "") (part "R_2"))
    )
    (comp (ref "R132")
      (value "DNM")
      (footprint "R0402 Reflow")
      (description "RES SMD 10K OHM 1% 1/16W 0402")
      (fields
        (field (name "TOLERANCE") "±1%")
        (field (name "02. DISTRIBUTOR PART NUMBER") "311-10.0KLRDKR-ND")
        (field (name "13. CREATED DATE/NAME") "AUG2018/Hören")
      )
      (libsource (lib "") (part "R_2"))
    )
    (comp (ref "R133")
      (value "10K")
      (footprint "R0402 Reflow")
      (description "RES SMD 10K OHM 1% 1/16W 0402")
      (fields
        (field (name "TOLERANCE") "±1%")
        (field (name "02. DISTRIBUTOR PART NUMBER") "311-10.0KLRDKR-ND")
        (field (name "13. CREATED DATE/NAME") "AUG2018/Hören")
      )
      (libsource (lib "") (part "R_2"))
    )
    (comp (ref "R134")
      (value "DNM")
      (footprint "R0402 Reflow")
      (description "RES SMD 10K OHM 1% 1/16W 0402")
      (fields
        (field (name "TOLERANCE") "±1%")
        (field (name "02. DISTRIBUTOR PART NUMBER") "311-10.0KLRDKR-ND")
        (field (name "13. CREATED DATE/NAME") "AUG2018/Hören")
      )
      (libsource (lib "chickenfood") (part "R"))
    )
    (comp (ref "R135")
      (value "1k")
      (footprint "R0402 Reflow")
      (description "RES SMD 1K OHM 1% 1/16W 0402")
      (fields
        (field (name "TOLERANCE") "±1%")
        (field (name "02. DISTRIBUTOR PART NUMBER") "YAG1254CT-ND")
        (field (name "13. CREATED DATE/NAME") "AUG2018/Hören")
      )
      (libsource (lib "chickenfood") (part "R"))
    )
    (comp (ref "R136")
      (value "10K")
      (footprint "R0402 Reflow")
      (description "RES SMD 10K OHM 1% 1/16W 0402")
      (fields
        (field (name "TOLERANCE") "±1%")
        (field (name "02. DISTRIBUTOR PART NUMBER") "311-10.0KLRDKR-ND")
        (field (name "13. CREATED DATE/NAME") "AUG2018/Hören")
      )
      (libsource (lib "chickenfood") (part "R"))
    )
    (comp (ref "R137")
      (value "10K")
      (footprint "R0402 Reflow")
      (description "RES SMD 10K OHM 1% 1/16W 0402")
      (fields
        (field (name "TOLERANCE") "±1%")
        (field (name "02. DISTRIBUTOR PART NUMBER") "311-10.0KLRDKR-ND")
        (field (name "13. CREATED DATE/NAME") "AUG2018/Hören")
      )
      (libsource (lib "chickenfood") (part "R"))
    )
    (comp (ref "R138")
      (value "10K")
      (footprint "R0402 Reflow")
      (description "RES SMD 10K OHM 1% 1/16W 0402")
      (fields
        (field (name "TOLERANCE") "±1%")
        (field (name "02. DISTRIBUTOR PART NUMBER") "311-10.0KLRDKR-ND")
        (field (name "13. CREATED DATE/NAME") "AUG2018/Hören")
      )
      (libsource (lib "") (part "R_2"))
    )
    (comp (ref "R139")
      (value "10K")
      (footprint "R0402 Reflow")
      (description "RES SMD 10K OHM 1% 1/16W 0402")
      (fields
        (field (name "TOLERANCE") "±1%")
        (field (name "02. DISTRIBUTOR PART NUMBER") "311-10.0KLRDKR-ND")
        (field (name "13. CREATED DATE/NAME") "AUG2018/Hören")
      )
      (libsource (lib "") (part "R_2"))
    )
    (comp (ref "R140")
      (value "DNM")
      (footprint "R0402 Reflow")
      (description "RES SMD 10K OHM 1% 1/16W 0402")
      (fields
        (field (name "TOLERANCE") "±1%")
        (field (name "02. DISTRIBUTOR PART NUMBER") "311-10.0KLRDKR-ND")
        (field (name "13. CREATED DATE/NAME") "AUG2018/Hören")
      )
      (libsource (lib "") (part "R_2"))
    )
    (comp (ref "R141")
      (value "1k")
      (footprint "R0402 Reflow")
      (description "RES SMD 1K OHM 1% 1/16W 0402")
      (fields
        (field (name "TOLERANCE") "±1%")
        (field (name "02. DISTRIBUTOR PART NUMBER") "YAG1254CT-ND")
        (field (name "13. CREATED DATE/NAME") "AUG2018/Hören")
      )
      (libsource (lib "chickenfood") (part "R"))
    )
    (comp (ref "TP6")
      (value "TP")
      (footprint "DualTestpoint 100mils")
      (description "Dual testpoint, pitch 2.54mm")
      (fields
        (field (name "02. DISTRIBUTOR PART NUMBER") "HMTSW-103-07-G-S-240")
        (field (name "13. CREATED DATE/NAME") "AUG2018/Hören")
      )
      (libsource (lib "PCB-Tester-Board-V1") (part "DualTestpoint 100mils"))
    )
    (comp (ref "TP7")
      (value "TP")
      (footprint "DualTestpoint 100mils")
      (description "Dual testpoint, pitch 2.54mm")
      (fields
        (field (name "02. DISTRIBUTOR PART NUMBER") "HMTSW-103-07-G-S-240")
        (field (name "13. CREATED DATE/NAME") "AUG2018/Hören")
      )
      (libsource (lib "PCB-Tester-Board-V1") (part "DualTestpoint 100mils"))
    )
    (comp (ref "TP8")
      (value "TP")
      (footprint "DualTestpoint 100mils")
      (description "Dual testpoint, pitch 2.54mm")
      (fields
        (field (name "02. DISTRIBUTOR PART NUMBER") "HMTSW-103-07-G-S-240")
        (field (name "13. CREATED DATE/NAME") "AUG2018/Hören")
      )
      (libsource (lib "PCB-Tester-Board-V1") (part "DualTestpoint 100mils"))
    )
    (comp (ref "TP9")
      (value "TP")
      (footprint "DualTestpoint 100mils")
      (description "Dual testpoint, pitch 2.54mm")
      (fields
        (field (name "02. DISTRIBUTOR PART NUMBER") "HMTSW-103-07-G-S-240")
        (field (name "13. CREATED DATE/NAME") "AUG2018/Hören")
      )
      (libsource (lib "PCB-Tester-Board-V1") (part "DualTestpoint 100mils"))
    )
    (comp (ref "U3")
      (value "U")
      (footprint "QFN4-7x7-56_IRPS5401M")
      (description "POL - SUPIRBUCK")
      (fields
        (field (name "MFR") "Infineon")
        (field (name "07. MANUFACTURER  PART NUMBER") "IRPS5401MTRPBF")
        (field (name "NICNAME") "IRPS5401M")
      )
      (libsource (lib "PCB-Tester-Board-V1") (part "IRPS5401M"))
    )
  )
  (nets
    (net (code "2") (name "/PG_A") (class "Default")
      (node (ref "Q30") (pin "1") (pinfunction "G_1") (pintype "passive"))
      (node (ref "R120") (pin "1") (pinfunction "1_1") (pintype "passive"))
      (node (ref "U3") (pin "26") (pinfunction "PG_A_26") (pintype "passive"))
    )
    (net (code "3") (name "/PG_B") (class "Default")
      (node (ref "Q78") (pin "1") (pinfunction "G_1") (pintype "passive"))
      (node (ref "R124") (pin "1") (pinfunction "1_1") (pintype "passive"))
      (node (ref "U3") (pin "30") (pinfunction "PG_B_30") (pintype "passive"))
    )
    (net (code "4") (name "/PG_C") (class "Default")
      (node (ref "Q79") (pin "1") (pinfunction "G_1") (pintype "passive"))
      (node (ref "R131") (pin "1") (pinfunction "1_1") (pintype "passive"))
      (node (ref "U3") (pin "27") (pinfunction "PG_C_27") (pintype "passive"))
    )
    (net (code "5") (name "/PG_D") (class "Default")
      (node (ref "Q80") (pin "1") (pinfunction "G_1") (pintype "passive"))
      (node (ref "R138") (pin "1") (pinfunction "1_1") (pintype "passive"))
      (node (ref "U3") (pin "16") (pinfunction "PG_D_16") (pintype "passive"))
    )
    (net (code "6") (name "/Vcc") (class "Default")
      (node (ref "C49") (pin "1") (pinfunction "1_1") (pintype "passive"))
      (node (ref "C50") (pin "1") (pinfunction "1_1") (pintype "passive"))
      (node (ref "R123") (pin "2") (pinfunction "2_2") (pintype "passive"))
      (node (ref "U3") (pin "29") (pinfunction "SLEEP#_29") (pintype "passive"))
      (node (ref "U3") (pin "48") (pinfunction "VCC_48") (pintype "passive"))
    )
    (net (code "7") (name "/Vin") (class "Default")
      (node (ref "C18") (pin "1") (pinfunction "1_1") (pintype "passive"))
      (node (ref "C19") (pin "1") (pinfunction "1_1") (pintype "passive"))
      (node (ref "C20") (pin "1") (pinfunction "1_1") (pintype "passive"))
      (node (ref "C21") (pin "1") (pinfunction "1_1") (pintype "passive"))
      (node (ref "C22") (pin "1") (pinfunction "1_1") (pintype "passive"))
      (node (ref "C23") (pin "1") (pinfunction "1_1") (pintype "passive"))
      (node (ref "C38") (pin "1") (pinfunction "1_1") (pintype "passive"))
      (node (ref "C41") (pin "1") (pinfunction "1_1") (pintype "passive"))
      (node (ref "C43") (pin "1") (pinfunction "1_1") (pintype "passive"))
      (node (ref "C44") (pin "1") (pinfunction "1_1") (pintype "passive"))
      (node (ref "C45") (pin "1") (pinfunction "1_1") (pintype "passive"))
      (node (ref "C47") (pin "1") (pinfunction "1_1") (pintype "passive"))
      (node (ref "C7") (pin "1") (pinfunction "1_1") (pintype "passive"))
      (node (ref "C8") (pin "1") (pinfunction "1_1") (pintype "passive"))
      (node (ref "U3") (pin "1") (pinfunction "VIN_D_1") (pintype "passive"))
      (node (ref "U3") (pin "12") (pinfunction "VIN_C_12") (pintype "passive"))
      (node (ref "U3") (pin "32") (pinfunction "VIN_B_32") (pintype "passive"))
      (node (ref "U3") (pin "39") (pinfunction "VIN_A_39") (pintype "passive"))
      (node (ref "U3") (pin "49") (pinfunction "VSUPPLY_49") (pintype "passive"))
    )
    (net (code "8") (name "/Vout1") (class "Default")
      (node (ref "C66") (pin "1") (pinfunction "1_1") (pintype "passive"))
      (node (ref "J5") (pin "2") (pinfunction "2_2") (pintype "passive"))
      (node (ref "J6") (pin "2") (pinfunction "2_2") (pintype "passive"))
    )
    (net (code "9") (name "/Vout2") (class "Default")
      (node (ref "C67") (pin "1") (pinfunction "1_1") (pintype "passive"))
      (node (ref "J7") (pin "2") (pinfunction "2_2") (pintype "passive"))
      (node (ref "J8") (pin "2") (pinfunction "2_2") (pintype "passive"))
    )
    (net (code "10") (name "/Vout3") (class "Default")
      (node (ref "C68") (pin "1") (pinfunction "1_1") (pintype "passive"))
      (node (ref "J10") (pin "2") (pinfunction "2_2") (pintype "passive"))
      (node (ref "J9") (pin "2") (pinfunction "2_2") (pintype "passive"))
    )
    (net (code "11") (name "/Vout4") (class "Default")
      (node (ref "C69") (pin "1") (pinfunction "1_1") (pintype "passive"))
      (node (ref "J11") (pin "2") (pinfunction "2_2") (pintype "passive"))
      (node (ref "J12") (pin "2") (pinfunction "2_2") (pintype "passive"))
    )
    (net (code "12") (name "/nPOR_F") (class "Default")
      (node (ref "Q98") (pin "3") (pinfunction "D_3") (pintype "passive"))
    )
    (net (code "14") (name "5V0") (class "Default")
      (node (ref "D10") (pin "1") (pinfunction "Anode_1") (pintype "passive"))
      (node (ref "D11") (pin "1") (pinfunction "Anode_1") (pintype "passive"))
      (node (ref "D12") (pin "1") (pinfunction "Anode_1") (pintype "passive"))
      (node (ref "D9") (pin "1") (pinfunction "Anode_1") (pintype "passive"))
      (node (ref "R120") (pin "2") (pinfunction "2_2") (pintype "passive"))
      (node (ref "R121") (pin "2") (pinfunction "2_2") (pintype "passive"))
      (node (ref "R124") (pin "2") (pinfunction "2_2") (pintype "passive"))
      (node (ref "R125") (pin "2") (pinfunction "2_2") (pintype "passive"))
      (node (ref "R131") (pin "2") (pinfunction "2_2") (pintype "passive"))
      (node (ref "R132") (pin "2") (pinfunction "2_2") (pintype "passive"))
      (node (ref "R138") (pin "2") (pinfunction "2_2") (pintype "passive"))
      (node (ref "R139") (pin "2") (pinfunction "2_2") (pintype "passive"))
    )
    (net (code "15") (name "GND") (class "Default")
      (node (ref "C18") (pin "2") (pinfunction "2_2") (pintype "passive"))
      (node (ref "C19") (pin "2") (pinfunction "2_2") (pintype "passive"))
      (node (ref "C20") (pin "2") (pinfunction "2_2") (pintype "passive"))
      (node (ref "C21") (pin "2") (pinfunction "2_2") (pintype "passive"))
      (node (ref "C22") (pin "2") (pinfunction "2_2") (pintype "passive"))
      (node (ref "C23") (pin "2") (pinfunction "2_2") (pintype "passive"))
      (node (ref "C24") (pin "2") (pinfunction "2_2") (pintype "passive"))
      (node (ref "C25") (pin "2") (pinfunction "2_2") (pintype "passive"))
      (node (ref "C26") (pin "2") (pinfunction "2_2") (pintype "passive"))
      (node (ref "C27") (pin "2") (pinfunction "2_2") (pintype "passive"))
      (node (ref "C28") (pin "2") (pinfunction "2_2") (pintype "passive"))
      (node (ref "C29") (pin "2") (pinfunction "2_2") (pintype "passive"))
      (node (ref "C30") (pin "2") (pinfunction "2_2") (pintype "passive"))
      (node (ref "C31") (pin "2") (pinfunction "2_2") (pintype "passive"))
      (node (ref "C32") (pin "2") (pinfunction "2_2") (pintype "passive"))
      (node (ref "C33") (pin "2") (pinfunction "2_2") (pintype "passive"))
      (node (ref "C34") (pin "2") (pinfunction "2_2") (pintype "passive"))
      (node (ref "C35") (pin "2") (pinfunction "2_2") (pintype "passive"))
      (node (ref "C38") (pin "2") (pinfunction "2_2") (pintype "passive"))
      (node (ref "C41") (pin "2") (pinfunction "2_2") (pintype "passive"))
      (node (ref "C42") (pin "2") (pinfunction "2_2") (pintype "passive"))
      (node (ref "C43") (pin "2") (pinfunction "2_2") (pintype "passive"))
      (node (ref "C44") (pin "2") (pinfunction "2_2") (pintype "passive"))
      (node (ref "C45") (pin "2") (pinfunction "2_2") (pintype "passive"))
      (node (ref "C47") (pin "2") (pinfunction "2_2") (pintype "passive"))
      (node (ref "C48") (pin "2") (pinfunction "2_2") (pintype "passive"))
      (node (ref "C49") (pin "2") (pinfunction "2_2") (pintype "passive"))
      (node (ref "C50") (pin "2") (pinfunction "2_2") (pintype "passive"))
      (node (ref "C51") (pin "2") (pinfunction "2_2") (pintype "passive"))
      (node (ref "C52") (pin "2") (pinfunction "2_2") (pintype "passive"))
      (node (ref "C53") (pin "2") (pinfunction "2_2") (pintype "passive"))
      (node (ref "C54") (pin "2") (pinfunction "2_2") (pintype "passive"))
      (node (ref "C56") (pin "2") (pinfunction "2_2") (pintype "passive"))
      (node (ref "C58") (pin "2") (pinfunction "2_2") (pintype "passive"))
      (node (ref "C59") (pin "2") (pinfunction "2_2") (pintype "passive"))
      (node (ref "C60") (pin "2") (pinfunction "2_2") (pintype "passive"))
      (node (ref "C66") (pin "2") (pinfunction "2_2") (pintype "passive"))
      (node (ref "C67") (pin "2") (pinfunction "2_2") (pintype "passive"))
      (node (ref "C68") (pin "2") (pinfunction "2_2") (pintype "passive"))
      (node (ref "C69") (pin "2") (pinfunction "2_2") (pintype "passive"))
      (node (ref "C7") (pin "2") (pinfunction "2_2") (pintype "passive"))
      (node (ref "C8") (pin "2") (pinfunction "2_2") (pintype "passive"))
      (node (ref "Q30") (pin "2") (pinfunction "S_2") (pintype "passive"))
      (node (ref "Q78") (pin "2") (pinfunction "S_2") (pintype "passive"))
      (node (ref "Q79") (pin "2") (pinfunction "S_2") (pintype "passive"))
      (node (ref "Q80") (pin "2") (pinfunction "S_2") (pintype "passive"))
      (node (ref "Q98") (pin "2") (pinfunction "S_2") (pintype "passive"))
      (node (ref "R122") (pin "2") (pinfunction "2_2") (pintype "passive"))
      (node (ref "R126") (pin "2") (pinfunction "2_2") (pintype "passive"))
      (node (ref "R133") (pin "2") (pinfunction "2_2") (pintype "passive"))
      (node (ref "R134") (pin "1") (pinfunction "1_1") (pintype "passive"))
      (node (ref "R136") (pin "1") (pinfunction "1_1") (pintype "passive"))
      (node (ref "R137") (pin "1") (pinfunction "1_1") (pintype "passive"))
      (node (ref "R140") (pin "2") (pinfunction "2_2") (pintype "passive"))
      (node (ref "R141") (pin "1") (pinfunction "1_1") (pintype "passive"))
      (node (ref "R95") (pin "1") (pinfunction "1_1") (pintype "passive"))
      (node (ref "R97") (pin "1") (pinfunction "1_1") (pintype "passive"))
      (node (ref "TP6") (pin "2") (pinfunction "2_2") (pintype "passive"))
      (node (ref "TP7") (pin "2") (pinfunction "2_2") (pintype "passive"))
      (node (ref "TP8") (pin "2") (pinfunction "2_2") (pintype "passive"))
      (node (ref "TP9") (pin "2") (pinfunction "2_2") (pintype "passive"))
      (node (ref "U3") (pin "22") (pinfunction "VIN_LDO_22") (pintype "passive"))
      (node (ref "U3") (pin "28") (pinfunction "EN_L_28") (pintype "passive"))
      (node (ref "U3") (pin "40") (pinfunction "RTN_A_40") (pintype "passive"))
      (node (ref "U3") (pin "50") (pinfunction "AGND_50") (pintype "passive"))
      (node (ref "U3") (pin "52") (pinfunction "SYNC_CLK_52") (pintype "passive"))
      (node (ref "U3") (pin "57") (pinfunction "GND_57") (pintype "passive"))
    )
    (net (code "16") (name "Net-(C24-Pad1)") (class "Default")
      (node (ref "C24") (pin "1") (pinfunction "1_1") (pintype "passive"))
      (node (ref "C25") (pin "1") (pinfunction "1_1") (pintype "passive"))
      (node (ref "C26") (pin "1") (pinfunction "1_1") (pintype "passive"))
      (node (ref "C42") (pin "1") (pinfunction "1_1") (pintype "passive"))
      (node (ref "J5") (pin "1") (pinfunction "1_1") (pintype "passive"))
      (node (ref "J6") (pin "1") (pinfunction "1_1") (pintype "passive"))
      (node (ref "L3") (pin "2") (pinfunction "2_2") (pintype "passive"))
      (node (ref "R94") (pin "2") (pinfunction "2_2") (pintype "passive"))
      (node (ref "TP6") (pin "1") (pinfunction "1_1") (pintype "passive"))
    )
    (net (code "17") (name "Net-(C27-Pad1)") (class "Default")
      (node (ref "C27") (pin "1") (pinfunction "1_1") (pintype "passive"))
      (node (ref "C28") (pin "1") (pinfunction "1_1") (pintype "passive"))
      (node (ref "C29") (pin "1") (pinfunction "1_1") (pintype "passive"))
      (node (ref "C48") (pin "1") (pinfunction "1_1") (pintype "passive"))
      (node (ref "J7") (pin "1") (pinfunction "1_1") (pintype "passive"))
      (node (ref "J8") (pin "1") (pinfunction "1_1") (pintype "passive"))
      (node (ref "L4") (pin "2") (pinfunction "2_2") (pintype "passive"))
      (node (ref "R96") (pin "2") (pinfunction "2_2") (pintype "passive"))
      (node (ref "TP7") (pin "1") (pinfunction "1_1") (pintype "passive"))
    )
    (net (code "18") (name "Net-(C30-Pad1)") (class "Default")
      (node (ref "C30") (pin "1") (pinfunction "1_1") (pintype "passive"))
      (node (ref "C31") (pin "1") (pinfunction "1_1") (pintype "passive"))
      (node (ref "C32") (pin "1") (pinfunction "1_1") (pintype "passive"))
      (node (ref "C56") (pin "1") (pinfunction "1_1") (pintype "passive"))
      (node (ref "J10") (pin "1") (pinfunction "1_1") (pintype "passive"))
      (node (ref "J9") (pin "1") (pinfunction "1_1") (pintype "passive"))
      (node (ref "L5") (pin "2") (pinfunction "2_2") (pintype "passive"))
      (node (ref "R130") (pin "2") (pinfunction "2_2") (pintype "passive"))
      (node (ref "TP8") (pin "1") (pinfunction "1_1") (pintype "passive"))
    )
    (net (code "19") (name "Net-(C33-Pad1)") (class "Default")
      (node (ref "C33") (pin "1") (pinfunction "1_1") (pintype "passive"))
      (node (ref "C34") (pin "1") (pinfunction "1_1") (pintype "passive"))
      (node (ref "C35") (pin "1") (pinfunction "1_1") (pintype "passive"))
      (node (ref "C60") (pin "1") (pinfunction "1_1") (pintype "passive"))
      (node (ref "J11") (pin "1") (pinfunction "1_1") (pintype "passive"))
      (node (ref "J12") (pin "1") (pinfunction "1_1") (pintype "passive"))
      (node (ref "L6") (pin "2") (pinfunction "2_2") (pintype "passive"))
      (node (ref "R135") (pin "2") (pinfunction "2_2") (pintype "passive"))
      (node (ref "TP9") (pin "1") (pinfunction "1_1") (pintype "passive"))
    )
    (net (code "20") (name "Net-(D9-Cathode)") (class "Default")
      (node (ref "D9") (pin "2") (pinfunction "Cathode_2") (pintype "passive"))
      (node (ref "R99") (pin "2") (pinfunction "2_2") (pintype "passive"))
    )
    (net (code "21") (name "Net-(D10-Cathode)") (class "Default")
      (node (ref "D10") (pin "2") (pinfunction "Cathode_2") (pintype "passive"))
      (node (ref "R101") (pin "2") (pinfunction "2_2") (pintype "passive"))
    )
    (net (code "22") (name "Net-(D11-Cathode)") (class "Default")
      (node (ref "D11") (pin "2") (pinfunction "Cathode_2") (pintype "passive"))
      (node (ref "R103") (pin "2") (pinfunction "2_2") (pintype "passive"))
    )
    (net (code "23") (name "Net-(D12-Cathode)") (class "Default")
      (node (ref "D12") (pin "2") (pinfunction "Cathode_2") (pintype "passive"))
      (node (ref "R105") (pin "2") (pinfunction "2_2") (pintype "passive"))
    )
    (net (code "24") (name "Net-(Q30-D)") (class "Default")
      (node (ref "Q30") (pin "3") (pinfunction "D_3") (pintype "passive"))
      (node (ref "R99") (pin "1") (pinfunction "1_1") (pintype "passive"))
    )
    (net (code "25") (name "Net-(Q78-D)") (class "Default")
      (node (ref "Q78") (pin "3") (pinfunction "D_3") (pintype "passive"))
      (node (ref "R101") (pin "1") (pinfunction "1_1") (pintype "passive"))
    )
    (net (code "26") (name "Net-(Q79-D)") (class "Default")
      (node (ref "Q79") (pin "3") (pinfunction "D_3") (pintype "passive"))
      (node (ref "R103") (pin "1") (pinfunction "1_1") (pintype "passive"))
    )
    (net (code "27") (name "Net-(Q80-D)") (class "Default")
      (node (ref "Q80") (pin "3") (pinfunction "D_3") (pintype "passive"))
      (node (ref "Q98") (pin "1") (pinfunction "G_1") (pintype "passive"))
      (node (ref "R105") (pin "1") (pinfunction "1_1") (pintype "passive"))
    )
    (net (code "28") (name "Net-(U3A-BOOT_A)") (class "Default")
      (node (ref "C40") (pin "1") (pinfunction "1_1") (pintype "passive"))
      (node (ref "U3") (pin "38") (pinfunction "BOOT_A_38") (pintype "passive"))
    )
    (net (code "29") (name "Net-(U3A-EN_A)") (class "Default")
      (node (ref "R121") (pin "1") (pinfunction "1_1") (pintype "passive"))
      (node (ref "R122") (pin "1") (pinfunction "1_1") (pintype "passive"))
      (node (ref "U3") (pin "42") (pinfunction "EN_A_42") (pintype "passive"))
    )
    (net (code "30") (name "Net-(U3A-FB_A)") (class "Default")
      (node (ref "R94") (pin "1") (pinfunction "1_1") (pintype "passive"))
      (node (ref "R95") (pin "2") (pinfunction "2_2") (pintype "passive"))
      (node (ref "U3") (pin "41") (pinfunction "FB_A_41") (pintype "passive"))
    )
    (net (code "31") (name "Net-(U3A-ISEN_A+)") (class "Default")
      (node (ref "U3") (pin "45") (pinfunction "ISEN_A-_45") (pintype "passive"))
      (node (ref "U3") (pin "46") (pinfunction "ISEN_A+_46") (pintype "passive"))
    )
    (net (code "32") (name "Net-(U3A-PHASE_A)") (class "Default")
      (node (ref "C40") (pin "2") (pinfunction "2_2") (pintype "passive"))
      (node (ref "L3") (pin "1") (pinfunction "1_1") (pintype "passive"))
      (node (ref "U3") (pin "36") (pinfunction "PHASE_A_36") (pintype "passive"))
    )
    (net (code "33") (name "Net-(U3B-BOOT_B)") (class "Default")
      (node (ref "C46") (pin "1") (pinfunction "1_1") (pintype "passive"))
      (node (ref "U3") (pin "33") (pinfunction "BOOT_B_33") (pintype "passive"))
    )
    (net (code "34") (name "Net-(U3B-EN_B)") (class "Default")
      (node (ref "R125") (pin "1") (pinfunction "1_1") (pintype "passive"))
      (node (ref "R126") (pin "1") (pinfunction "1_1") (pintype "passive"))
      (node (ref "U3") (pin "44") (pinfunction "EN_B_44") (pintype "passive"))
    )
    (net (code "35") (name "Net-(U3B-FB_B)") (class "Default")
      (node (ref "R96") (pin "1") (pinfunction "1_1") (pintype "passive"))
      (node (ref "R97") (pin "2") (pinfunction "2_2") (pintype "passive"))
      (node (ref "U3") (pin "31") (pinfunction "FB_B_31") (pintype "passive"))
    )
    (net (code "36") (name "Net-(U3B-PHASE_B)") (class "Default")
      (node (ref "C46") (pin "2") (pinfunction "2_2") (pintype "passive"))
      (node (ref "L4") (pin "1") (pinfunction "1_1") (pintype "passive"))
      (node (ref "U3") (pin "34") (pinfunction "PHASE_B_34") (pintype "passive"))
    )
    (net (code "37") (name "Net-(U3C-BOOT_C)") (class "Default")
      (node (ref "C55") (pin "1") (pinfunction "1_1") (pintype "passive"))
      (node (ref "U3") (pin "11") (pinfunction "BOOT_C_11") (pintype "passive"))
    )
    (net (code "38") (name "Net-(U3C-EN_C)") (class "Default")
      (node (ref "R132") (pin "1") (pinfunction "1_1") (pintype "passive"))
      (node (ref "R133") (pin "1") (pinfunction "1_1") (pintype "passive"))
      (node (ref "U3") (pin "51") (pinfunction "EN_C_51") (pintype "passive"))
    )
    (net (code "39") (name "Net-(U3C-FB_C)") (class "Default")
      (node (ref "R130") (pin "1") (pinfunction "1_1") (pintype "passive"))
      (node (ref "R134") (pin "2") (pinfunction "2_2") (pintype "passive"))
      (node (ref "U3") (pin "15") (pinfunction "FB_C_15") (pintype "passive"))
    )
    (net (code "40") (name "Net-(U3C-PHASE_C)") (class "Default")
      (node (ref "C55") (pin "2") (pinfunction "2_2") (pintype "passive"))
      (node (ref "L5") (pin "1") (pinfunction "1_1") (pintype "passive"))
      (node (ref "U3") (pin "8") (pinfunction "PHASE_C_8") (pintype "passive"))
    )
    (net (code "41") (name "Net-(U3D-BOOT_D)") (class "Default")
      (node (ref "C57") (pin "1") (pinfunction "1_1") (pintype "passive"))
      (node (ref "U3") (pin "4") (pinfunction "BOOT_D_4") (pintype "passive"))
    )
    (net (code "42") (name "Net-(U3D-EN_D)") (class "Default")
      (node (ref "R139") (pin "1") (pinfunction "1_1") (pintype "passive"))
      (node (ref "R140") (pin "1") (pinfunction "1_1") (pintype "passive"))
      (node (ref "U3") (pin "53") (pinfunction "EN_D_53") (pintype "passive"))
    )
    (net (code "43") (name "Net-(U3D-FB_D)") (class "Default")
      (node (ref "R135") (pin "1") (pinfunction "1_1") (pintype "passive"))
      (node (ref "R141") (pin "2") (pinfunction "2_2") (pintype "passive"))
      (node (ref "U3") (pin "56") (pinfunction "FB_D_56") (pintype "passive"))
    )
    (net (code "44") (name "Net-(U3D-PHASE_D)") (class "Default")
      (node (ref "C57") (pin "2") (pinfunction "2_2") (pintype "passive"))
      (node (ref "L6") (pin "1") (pinfunction "1_1") (pintype "passive"))
      (node (ref "U3") (pin "5") (pinfunction "PHASE_D_5") (pintype "passive"))
    )
    (net (code "45") (name "Net-(U3E-1V8)") (class "Default")
      (node (ref "C54") (pin "1") (pinfunction "1_1") (pintype "passive"))
      (node (ref "U3") (pin "21") (pinfunction "1V8_21") (pintype "passive"))
    )
    (net (code "46") (name "Net-(U3E-ADDR_PROT)") (class "Default")
      (node (ref "C59") (pin "1") (pinfunction "1_1") (pintype "passive"))
      (node (ref "R137") (pin "2") (pinfunction "2_2") (pintype "passive"))
      (node (ref "U3") (pin "55") (pinfunction "ADDR_PROT_55") (pintype "passive"))
    )
    (net (code "47") (name "Net-(U3E-ALERT#)") (class "Default")
      (node (ref "R127") (pin "1") (pinfunction "1_1") (pintype "passive"))
      (node (ref "U3") (pin "17") (pinfunction "ALERT#_17") (pintype "passive"))
    )
    (net (code "48") (name "Net-(U3E-CLK)") (class "Default")
      (node (ref "R128") (pin "1") (pinfunction "1_1") (pintype "passive"))
      (node (ref "U3") (pin "18") (pinfunction "CLK_18") (pintype "passive"))
    )
    (net (code "49") (name "Net-(U3E-DATA)") (class "Default")
      (node (ref "R129") (pin "1") (pinfunction "1_1") (pintype "passive"))
      (node (ref "U3") (pin "19") (pinfunction "DATA_19") (pintype "passive"))
    )
    (net (code "50") (name "Net-(U3E-MTP)") (class "Default")
      (node (ref "C58") (pin "1") (pinfunction "1_1") (pintype "passive"))
      (node (ref "R136") (pin "2") (pinfunction "2_2") (pintype "passive"))
      (node (ref "U3") (pin "54") (pinfunction "MTP_54") (pintype "passive"))
    )
    (net (code "51") (name "Net-(U3E-VDDIO)") (class "Default")
      (node (ref "C53") (pin "1") (pinfunction "1_1") (pintype "passive"))
      (node (ref "R127") (pin "2") (pinfunction "2_2") (pintype "passive"))
      (node (ref "R128") (pin "2") (pinfunction "2_2") (pintype "passive"))
      (node (ref "R129") (pin "2") (pinfunction "2_2") (pintype "passive"))
      (node (ref "U3") (pin "20") (pinfunction "VDDIO_20") (pintype "passive"))
    )
    (net (code "52") (name "Net-(U3E-VDRV)") (class "Default")
      (node (ref "C51") (pin "1") (pinfunction "1_1") (pintype "passive"))
      (node (ref "C52") (pin "1") (pinfunction "1_1") (pintype "passive"))
      (node (ref "R123") (pin "1") (pinfunction "1_1") (pintype "passive"))
      (node (ref "U3") (pin "47") (pinfunction "VDRV_47") (pintype "passive"))
    )
    (net (code "53") (name "unconnected-(U3A-PWM_A-Pad43)") (class "Default")
      (node (ref "U3") (pin "43") (pinfunction "PWM_A_43") (pintype "passive+no_connect"))
    )
    (net (code "54") (name "unconnected-(U3E-FB_L-Pad24)") (class "Default")
      (node (ref "U3") (pin "24") (pinfunction "FB_L_24") (pintype "passive+no_connect"))
    )
    (net (code "55") (name "unconnected-(U3E-PG_L-Pad25)") (class "Default")
      (node (ref "U3") (pin "25") (pinfunction "PG_L_25") (pintype "passive+no_connect"))
    )
    (net (code "56") (name "unconnected-(U3E-VO_LDO-Pad23)") (class "Default")
      (node (ref "U3") (pin "23") (pinfunction "VO_LDO_23") (pintype "passive+no_connect"))
    )
  )
)
